# bitfur_adapter.net
KiCad netlist of a schematic drawn in EAGLE
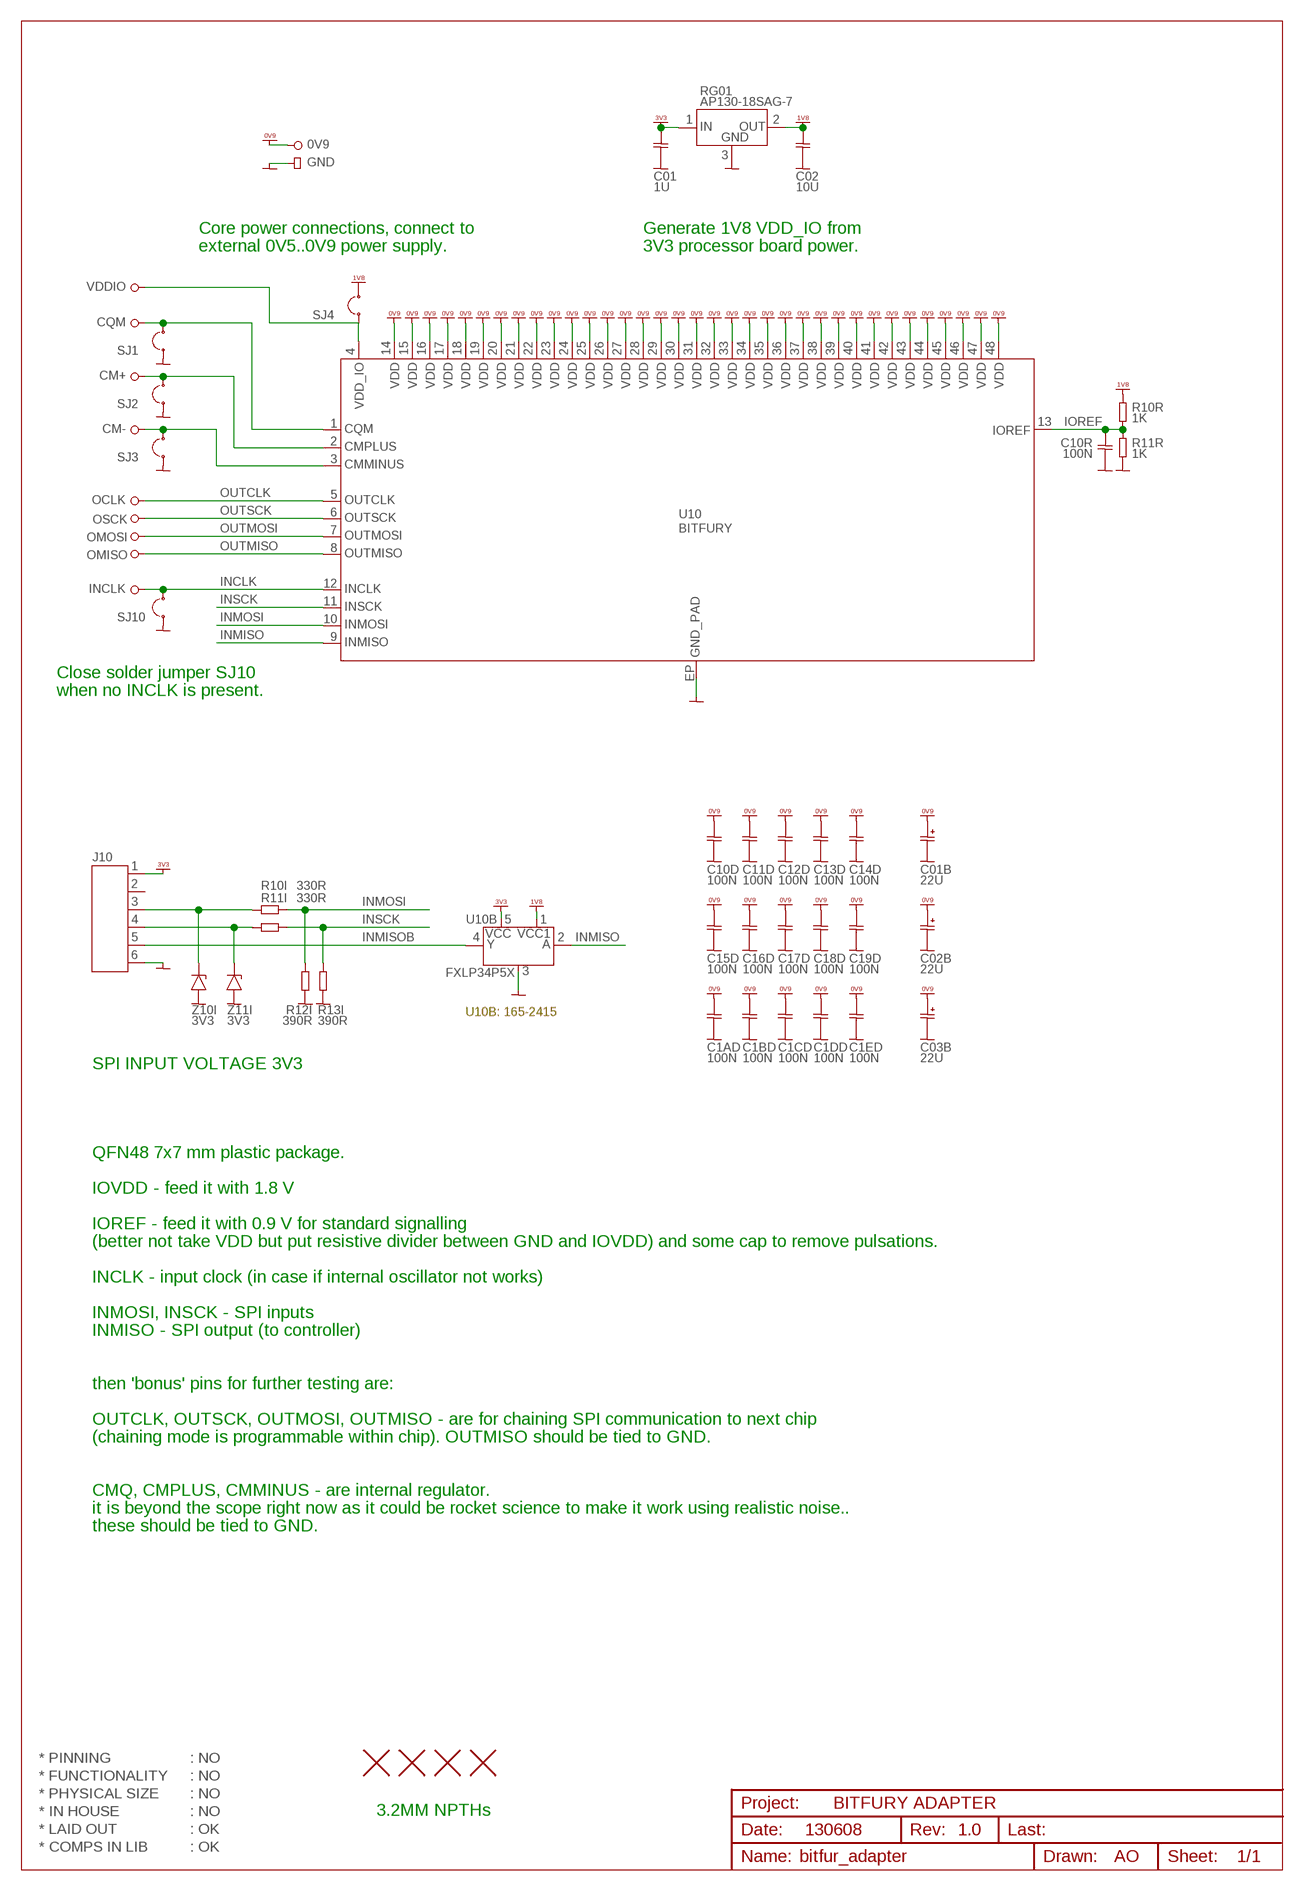
[diagram p0: schematic, sheet 1]

(export (version "E")
  (design (tool "Eeschema 10.0.6"))
  (components
    (comp (ref "0V9")
      (value "PIN_TEST_BIG")
      (footprint "eagle-import:PAD_HOLE_BIG")
      (libsource (lib "eagle-import") (part "PIN_TEST_BIG"))
    )
    (comp (ref "C01")
      (value "1U")
      (footprint "eagle-import:CAP0603")
      (libsource (lib "eagle-import") (part "CAP0603"))
    )
    (comp (ref "C1AD")
      (value "100N")
      (footprint "eagle-import:CAP0402")
      (libsource (lib "eagle-import") (part "CAP0402"))
    )
    (comp (ref "C01B")
      (value "22U")
      (footprint "eagle-import:ECAP_SMA")
      (libsource (lib "eagle-import") (part "ECAP_SMA"))
    )
    (comp (ref "C1BD")
      (value "100N")
      (footprint "eagle-import:CAP0402")
      (libsource (lib "eagle-import") (part "CAP0402"))
    )
    (comp (ref "C1CD")
      (value "100N")
      (footprint "eagle-import:CAP0402")
      (libsource (lib "eagle-import") (part "CAP0402"))
    )
    (comp (ref "C1DD")
      (value "100N")
      (footprint "eagle-import:CAP0402")
      (libsource (lib "eagle-import") (part "CAP0402"))
    )
    (comp (ref "C1ED")
      (value "100N")
      (footprint "eagle-import:CAP0402")
      (libsource (lib "eagle-import") (part "CAP0402"))
    )
    (comp (ref "C02")
      (value "10U")
      (footprint "eagle-import:CAP0603")
      (libsource (lib "eagle-import") (part "CAP0603"))
    )
    (comp (ref "C02B")
      (value "22U")
      (footprint "eagle-import:ECAP_SMA")
      (libsource (lib "eagle-import") (part "ECAP_SMA"))
    )
    (comp (ref "C03B")
      (value "22U")
      (footprint "eagle-import:ECAP_SMA")
      (libsource (lib "eagle-import") (part "ECAP_SMA"))
    )
    (comp (ref "C10D")
      (value "100N")
      (footprint "eagle-import:CAP0402")
      (libsource (lib "eagle-import") (part "CAP0402"))
    )
    (comp (ref "C10R")
      (value "100N")
      (footprint "eagle-import:CAP0402")
      (libsource (lib "eagle-import") (part "CAP0402"))
    )
    (comp (ref "C11D")
      (value "100N")
      (footprint "eagle-import:CAP0402")
      (libsource (lib "eagle-import") (part "CAP0402"))
    )
    (comp (ref "C12D")
      (value "100N")
      (footprint "eagle-import:CAP0402")
      (libsource (lib "eagle-import") (part "CAP0402"))
    )
    (comp (ref "C13D")
      (value "100N")
      (footprint "eagle-import:CAP0402")
      (libsource (lib "eagle-import") (part "CAP0402"))
    )
    (comp (ref "C14D")
      (value "100N")
      (footprint "eagle-import:CAP0402")
      (libsource (lib "eagle-import") (part "CAP0402"))
    )
    (comp (ref "C15D")
      (value "100N")
      (footprint "eagle-import:CAP0402")
      (libsource (lib "eagle-import") (part "CAP0402"))
    )
    (comp (ref "C16D")
      (value "100N")
      (footprint "eagle-import:CAP0402")
      (libsource (lib "eagle-import") (part "CAP0402"))
    )
    (comp (ref "C17D")
      (value "100N")
      (footprint "eagle-import:CAP0402")
      (libsource (lib "eagle-import") (part "CAP0402"))
    )
    (comp (ref "C18D")
      (value "100N")
      (footprint "eagle-import:CAP0402")
      (libsource (lib "eagle-import") (part "CAP0402"))
    )
    (comp (ref "C19D")
      (value "100N")
      (footprint "eagle-import:CAP0402")
      (libsource (lib "eagle-import") (part "CAP0402"))
    )
    (comp (ref "CM+")
      (value "PIN_TEST")
      (footprint "eagle-import:PAD_HOLE_0.8MM")
      (libsource (lib "eagle-import") (part "PIN_TEST"))
    )
    (comp (ref "CM-")
      (value "PIN_TEST")
      (footprint "eagle-import:PAD_HOLE_0.8MM")
      (libsource (lib "eagle-import") (part "PIN_TEST"))
    )
    (comp (ref "CQM")
      (value "PIN_TEST")
      (footprint "eagle-import:PAD_HOLE_0.8MM")
      (libsource (lib "eagle-import") (part "PIN_TEST"))
    )
    (comp (ref "H1")
      (value "HOLE_NPTH_3.2MM")
      (footprint "eagle-import:HOLE_NPTH_3.2MM")
      (libsource (lib "eagle-import") (part "HOLE_NPTH_3.2MM"))
    )
    (comp (ref "H2")
      (value "HOLE_NPTH_3.2MM")
      (footprint "eagle-import:HOLE_NPTH_3.2MM")
      (libsource (lib "eagle-import") (part "HOLE_NPTH_3.2MM"))
    )
    (comp (ref "H3")
      (value "HOLE_NPTH_3.2MM")
      (footprint "eagle-import:HOLE_NPTH_3.2MM")
      (libsource (lib "eagle-import") (part "HOLE_NPTH_3.2MM"))
    )
    (comp (ref "H4")
      (value "HOLE_NPTH_3.2MM")
      (footprint "eagle-import:HOLE_NPTH_3.2MM")
      (libsource (lib "eagle-import") (part "HOLE_NPTH_3.2MM"))
    )
    (comp (ref "INCLK")
      (value "PIN_TEST")
      (footprint "eagle-import:PAD_HOLE_0.8MM")
      (libsource (lib "eagle-import") (part "PIN_TEST"))
    )
    (comp (ref "J10")
      (value "CON_MICROMATCH_6F-TOP")
      (footprint "eagle-import:CON_MICROMATCH_TOP_6F")
      (libsource (lib "eagle-import") (part "CON_MICROMATCH_6F-TOP"))
    )
    (comp (ref "OCLK")
      (value "PIN_TEST")
      (footprint "eagle-import:PAD_HOLE_0.8MM")
      (libsource (lib "eagle-import") (part "PIN_TEST"))
    )
    (comp (ref "OMISO")
      (value "PIN_TEST")
      (footprint "eagle-import:PAD_HOLE_0.8MM")
      (libsource (lib "eagle-import") (part "PIN_TEST"))
    )
    (comp (ref "OMOSI")
      (value "PIN_TEST")
      (footprint "eagle-import:PAD_HOLE_0.8MM")
      (libsource (lib "eagle-import") (part "PIN_TEST"))
    )
    (comp (ref "OSCK")
      (value "PIN_TEST")
      (footprint "eagle-import:PAD_HOLE_0.8MM")
      (libsource (lib "eagle-import") (part "PIN_TEST"))
    )
    (comp (ref "R10I")
      (value "330R")
      (footprint "eagle-import:RES0603")
      (libsource (lib "eagle-import") (part "RES0603"))
    )
    (comp (ref "R10R")
      (value "1K")
      (footprint "eagle-import:RES0402")
      (libsource (lib "eagle-import") (part "RES0402"))
    )
    (comp (ref "R11I")
      (value "330R")
      (footprint "eagle-import:RES0603")
      (libsource (lib "eagle-import") (part "RES0603"))
    )
    (comp (ref "R11R")
      (value "1K")
      (footprint "eagle-import:RES0402")
      (libsource (lib "eagle-import") (part "RES0402"))
    )
    (comp (ref "R12I")
      (value "390R")
      (footprint "eagle-import:RES0603")
      (libsource (lib "eagle-import") (part "RES0603"))
    )
    (comp (ref "R13I")
      (value "390R")
      (footprint "eagle-import:RES0603")
      (libsource (lib "eagle-import") (part "RES0603"))
    )
    (comp (ref "RG01")
      (value "AP130-18SAG-7")
      (footprint "eagle-import:SOT23")
      (libsource (lib "eagle-import") (part "AP130-18SAG-7"))
    )
    (comp (ref "SJ1")
      (value "SJ2SJ2-S")
      (footprint "eagle-import:SJ2-S")
      (libsource (lib "eagle-import") (part "SJ2SJ2-S"))
    )
    (comp (ref "SJ2")
      (value "SJ2SJ2-S")
      (footprint "eagle-import:SJ2-S")
      (libsource (lib "eagle-import") (part "SJ2SJ2-S"))
    )
    (comp (ref "SJ3")
      (value "SJ2SJ2-S")
      (footprint "eagle-import:SJ2-S")
      (libsource (lib "eagle-import") (part "SJ2SJ2-S"))
    )
    (comp (ref "SJ4")
      (value "SJ2SJ2-S")
      (footprint "eagle-import:SJ2-S")
      (libsource (lib "eagle-import") (part "SJ2SJ2-S"))
    )
    (comp (ref "SJ10")
      (value "SJ2SJ2-S")
      (footprint "eagle-import:SJ2-S")
      (libsource (lib "eagle-import") (part "SJ2SJ2-S"))
    )
    (comp (ref "U$83")
      (value "PIN_GND")
      (footprint "eagle-import:PAD_HOLE_SQR_1.8MM")
      (libsource (lib "eagle-import") (part "PIN_GND"))
    )
    (comp (ref "U10")
      (value "BITFURY")
      (footprint "eagle-import:QNF48")
      (libsource (lib "eagle-import") (part "BITFURY"))
    )
    (comp (ref "U10B")
      (value "FXLP34P5X")
      (footprint "eagle-import:SOT23-5")
      (libsource (lib "eagle-import") (part "FXLP34P5X"))
    )
    (comp (ref "VDDIO")
      (value "PIN_TEST")
      (footprint "eagle-import:PAD_HOLE_0.8MM")
      (libsource (lib "eagle-import") (part "PIN_TEST"))
    )
    (comp (ref "Z10I")
      (value "3V3")
      (footprint "eagle-import:ZENER_SOD123")
      (libsource (lib "eagle-import") (part "ZENER_SOD123"))
    )
    (comp (ref "Z11I")
      (value "3V3")
      (footprint "eagle-import:ZENER_SOD123")
      (libsource (lib "eagle-import") (part "ZENER_SOD123"))
    )
  )
  (nets
    (net (code "1") (name "/INCLK") (class "Default")
      (node (ref "INCLK") (pin "1") (pinfunction "P$1_1") (pintype "passive"))
      (node (ref "SJ10") (pin "2") (pinfunction "P$2_2") (pintype "passive"))
      (node (ref "U10") (pin "12") (pinfunction "12.INCLK_12") (pintype "output"))
    )
    (net (code "2") (name "/INMISO") (class "Default")
      (node (ref "U10") (pin "9") (pinfunction "9.INMISO_9") (pintype "output"))
      (node (ref "U10B") (pin "2") (pinfunction "2.A_2") (pintype "passive"))
    )
    (net (code "3") (name "/INMISOB") (class "Default")
      (node (ref "J10") (pin "5") (pinfunction "5_5") (pintype "passive"))
      (node (ref "U10B") (pin "4") (pinfunction "4.Y_4") (pintype "passive"))
    )
    (net (code "4") (name "/INMOSI") (class "Default")
      (node (ref "R10I") (pin "2") (pinfunction "2_2") (pintype "passive"))
      (node (ref "R12I") (pin "2") (pinfunction "2_2") (pintype "passive"))
      (node (ref "U10") (pin "10") (pinfunction "10.INMOSI_10") (pintype "output"))
    )
    (net (code "5") (name "/INSCK") (class "Default")
      (node (ref "R11I") (pin "2") (pinfunction "2_2") (pintype "passive"))
      (node (ref "R13I") (pin "2") (pinfunction "2_2") (pintype "passive"))
      (node (ref "U10") (pin "11") (pinfunction "11.INSCK_11") (pintype "input"))
    )
    (net (code "6") (name "/IOREF") (class "Default")
      (node (ref "C10R") (pin "1") (pinfunction "1_1") (pintype "passive"))
      (node (ref "R10R") (pin "2") (pinfunction "2_2") (pintype "passive"))
      (node (ref "R11R") (pin "1") (pinfunction "1_1") (pintype "passive"))
      (node (ref "U10") (pin "13") (pinfunction "13.IOREF_13") (pintype "passive"))
    )
    (net (code "7") (name "/OUTCLK") (class "Default")
      (node (ref "OCLK") (pin "1") (pinfunction "P$1_1") (pintype "passive"))
      (node (ref "U10") (pin "5") (pinfunction "5.OUTCLK_5") (pintype "output"))
    )
    (net (code "8") (name "/OUTMISO") (class "Default")
      (node (ref "OMISO") (pin "1") (pinfunction "P$1_1") (pintype "passive"))
      (node (ref "U10") (pin "8") (pinfunction "8.OUTMISO_8") (pintype "output"))
    )
    (net (code "9") (name "/OUTMOSI") (class "Default")
      (node (ref "OMOSI") (pin "1") (pinfunction "P$1_1") (pintype "passive"))
      (node (ref "U10") (pin "7") (pinfunction "7.OUTMOSI_7") (pintype "output"))
    )
    (net (code "10") (name "/OUTSCK") (class "Default")
      (node (ref "OSCK") (pin "1") (pinfunction "P$1_1") (pintype "passive"))
      (node (ref "U10") (pin "6") (pinfunction "6.OUTSCK_6") (pintype "input"))
    )
    (net (code "11") (name "GND") (class "Default")
      (node (ref "C01") (pin "2") (pinfunction "2_2") (pintype "passive"))
      (node (ref "C01B") (pin "-") (pinfunction "-_-") (pintype "passive"))
      (node (ref "C02") (pin "2") (pinfunction "2_2") (pintype "passive"))
      (node (ref "C02B") (pin "-") (pinfunction "-_-") (pintype "passive"))
      (node (ref "C03B") (pin "-") (pinfunction "-_-") (pintype "passive"))
      (node (ref "C10D") (pin "2") (pinfunction "2_2") (pintype "passive"))
      (node (ref "C10R") (pin "2") (pinfunction "2_2") (pintype "passive"))
      (node (ref "C11D") (pin "2") (pinfunction "2_2") (pintype "passive"))
      (node (ref "C12D") (pin "2") (pinfunction "2_2") (pintype "passive"))
      (node (ref "C13D") (pin "2") (pinfunction "2_2") (pintype "passive"))
      (node (ref "C14D") (pin "2") (pinfunction "2_2") (pintype "passive"))
      (node (ref "C15D") (pin "2") (pinfunction "2_2") (pintype "passive"))
      (node (ref "C16D") (pin "2") (pinfunction "2_2") (pintype "passive"))
      (node (ref "C17D") (pin "2") (pinfunction "2_2") (pintype "passive"))
      (node (ref "C18D") (pin "2") (pinfunction "2_2") (pintype "passive"))
      (node (ref "C19D") (pin "2") (pinfunction "2_2") (pintype "passive"))
      (node (ref "C1AD") (pin "2") (pinfunction "2_2") (pintype "passive"))
      (node (ref "C1BD") (pin "2") (pinfunction "2_2") (pintype "passive"))
      (node (ref "C1CD") (pin "2") (pinfunction "2_2") (pintype "passive"))
      (node (ref "C1DD") (pin "2") (pinfunction "2_2") (pintype "passive"))
      (node (ref "C1ED") (pin "2") (pinfunction "2_2") (pintype "passive"))
      (node (ref "J10") (pin "6") (pinfunction "6_6") (pintype "passive"))
      (node (ref "R11R") (pin "2") (pinfunction "2_2") (pintype "passive"))
      (node (ref "R12I") (pin "1") (pinfunction "1_1") (pintype "passive"))
      (node (ref "R13I") (pin "1") (pinfunction "1_1") (pintype "passive"))
      (node (ref "RG01") (pin "3") (pinfunction "3.GND_3") (pintype "passive"))
      (node (ref "SJ1") (pin "1") (pinfunction "P$1_1") (pintype "passive"))
      (node (ref "SJ10") (pin "1") (pinfunction "P$1_1") (pintype "passive"))
      (node (ref "SJ2") (pin "1") (pinfunction "P$1_1") (pintype "passive"))
      (node (ref "SJ3") (pin "1") (pinfunction "P$1_1") (pintype "passive"))
      (node (ref "U$83") (pin "1") (pinfunction "P$1_1") (pintype "passive"))
      (node (ref "U10") (pin "EP") (pinfunction "EP.VSS_EP_EP") (pintype "passive"))
      (node (ref "U10") (pin "V1") (pinfunction "EP.VSS_EP_V1") (pintype "passive"))
      (node (ref "U10") (pin "V10") (pinfunction "EP.VSS_EP_V10") (pintype "passive"))
      (node (ref "U10") (pin "V11") (pinfunction "EP.VSS_EP_V11") (pintype "passive"))
      (node (ref "U10") (pin "V12") (pinfunction "EP.VSS_EP_V12") (pintype "passive"))
      (node (ref "U10") (pin "V13") (pinfunction "EP.VSS_EP_V13") (pintype "passive"))
      (node (ref "U10") (pin "V14") (pinfunction "EP.VSS_EP_V14") (pintype "passive"))
      (node (ref "U10") (pin "V15") (pinfunction "EP.VSS_EP_V15") (pintype "passive"))
      (node (ref "U10") (pin "V16") (pinfunction "EP.VSS_EP_V16") (pintype "passive"))
      (node (ref "U10") (pin "V17") (pinfunction "EP.VSS_EP_V17") (pintype "passive"))
      (node (ref "U10") (pin "V18") (pinfunction "EP.VSS_EP_V18") (pintype "passive"))
      (node (ref "U10") (pin "V19") (pinfunction "EP.VSS_EP_V19") (pintype "passive"))
      (node (ref "U10") (pin "V2") (pinfunction "EP.VSS_EP_V2") (pintype "passive"))
      (node (ref "U10") (pin "V20") (pinfunction "EP.VSS_EP_V20") (pintype "passive"))
      (node (ref "U10") (pin "V21") (pinfunction "EP.VSS_EP_V21") (pintype "passive"))
      (node (ref "U10") (pin "V22") (pinfunction "EP.VSS_EP_V22") (pintype "passive"))
      (node (ref "U10") (pin "V23") (pinfunction "EP.VSS_EP_V23") (pintype "passive"))
      (node (ref "U10") (pin "V24") (pinfunction "EP.VSS_EP_V24") (pintype "passive"))
      (node (ref "U10") (pin "V25") (pinfunction "EP.VSS_EP_V25") (pintype "passive"))
      (node (ref "U10") (pin "V3") (pinfunction "EP.VSS_EP_V3") (pintype "passive"))
      (node (ref "U10") (pin "V4") (pinfunction "EP.VSS_EP_V4") (pintype "passive"))
      (node (ref "U10") (pin "V5") (pinfunction "EP.VSS_EP_V5") (pintype "passive"))
      (node (ref "U10") (pin "V6") (pinfunction "EP.VSS_EP_V6") (pintype "passive"))
      (node (ref "U10") (pin "V7") (pinfunction "EP.VSS_EP_V7") (pintype "passive"))
      (node (ref "U10") (pin "V8") (pinfunction "EP.VSS_EP_V8") (pintype "passive"))
      (node (ref "U10") (pin "V9") (pinfunction "EP.VSS_EP_V9") (pintype "passive"))
      (node (ref "U10B") (pin "3") (pinfunction "3.GND_3") (pintype "passive"))
      (node (ref "Z10I") (pin "1") (pinfunction "+_1") (pintype "passive"))
      (node (ref "Z11I") (pin "1") (pinfunction "+_1") (pintype "passive"))
    )
    (net (code "12") (name "Net-(CM+-P$1)") (class "Default")
      (node (ref "CM+") (pin "1") (pinfunction "P$1_1") (pintype "passive"))
      (node (ref "SJ2") (pin "2") (pinfunction "P$2_2") (pintype "passive"))
      (node (ref "U10") (pin "2") (pinfunction "2.CMPLUS_2") (pintype "passive"))
    )
    (net (code "13") (name "Net-(CM--P$1)") (class "Default")
      (node (ref "CM-") (pin "1") (pinfunction "P$1_1") (pintype "passive"))
      (node (ref "SJ3") (pin "2") (pinfunction "P$2_2") (pintype "passive"))
      (node (ref "U10") (pin "3") (pinfunction "3.CMMINUS_3") (pintype "passive"))
    )
    (net (code "14") (name "Net-(CQM-P$1)") (class "Default")
      (node (ref "CQM") (pin "1") (pinfunction "P$1_1") (pintype "passive"))
      (node (ref "SJ1") (pin "2") (pinfunction "P$2_2") (pintype "passive"))
      (node (ref "U10") (pin "1") (pinfunction "1.QCM_1") (pintype "bidirectional"))
    )
    (net (code "15") (name "Net-(SJ4-P$1)") (class "Default")
      (node (ref "SJ4") (pin "1") (pinfunction "P$1_1") (pintype "passive"))
      (node (ref "U10") (pin "4") (pinfunction "4.VDD_IO_4") (pintype "passive"))
      (node (ref "VDDIO") (pin "1") (pinfunction "P$1_1") (pintype "passive"))
    )
    (net (code "16") (name "Net-(Z10I--)") (class "Default")
      (node (ref "J10") (pin "3") (pinfunction "3_3") (pintype "passive"))
      (node (ref "R10I") (pin "1") (pinfunction "1_1") (pintype "passive"))
      (node (ref "Z10I") (pin "2") (pinfunction "-_2") (pintype "passive"))
    )
    (net (code "17") (name "Net-(Z11I--)") (class "Default")
      (node (ref "J10") (pin "4") (pinfunction "4_4") (pintype "passive"))
      (node (ref "R11I") (pin "1") (pinfunction "1_1") (pintype "passive"))
      (node (ref "Z11I") (pin "2") (pinfunction "-_2") (pintype "passive"))
    )
    (net (code "18") (name "VCC_0V9") (class "Default")
      (node (ref "0V9") (pin "1") (pinfunction "P$1_1") (pintype "passive"))
      (node (ref "C01B") (pin "+") (pinfunction "+_+") (pintype "passive"))
      (node (ref "C02B") (pin "+") (pinfunction "+_+") (pintype "passive"))
      (node (ref "C03B") (pin "+") (pinfunction "+_+") (pintype "passive"))
      (node (ref "C10D") (pin "1") (pinfunction "1_1") (pintype "passive"))
      (node (ref "C11D") (pin "1") (pinfunction "1_1") (pintype "passive"))
      (node (ref "C12D") (pin "1") (pinfunction "1_1") (pintype "passive"))
      (node (ref "C13D") (pin "1") (pinfunction "1_1") (pintype "passive"))
      (node (ref "C14D") (pin "1") (pinfunction "1_1") (pintype "passive"))
      (node (ref "C15D") (pin "1") (pinfunction "1_1") (pintype "passive"))
      (node (ref "C16D") (pin "1") (pinfunction "1_1") (pintype "passive"))
      (node (ref "C17D") (pin "1") (pinfunction "1_1") (pintype "passive"))
      (node (ref "C18D") (pin "1") (pinfunction "1_1") (pintype "passive"))
      (node (ref "C19D") (pin "1") (pinfunction "1_1") (pintype "passive"))
      (node (ref "C1AD") (pin "1") (pinfunction "1_1") (pintype "passive"))
      (node (ref "C1BD") (pin "1") (pinfunction "1_1") (pintype "passive"))
      (node (ref "C1CD") (pin "1") (pinfunction "1_1") (pintype "passive"))
      (node (ref "C1DD") (pin "1") (pinfunction "1_1") (pintype "passive"))
      (node (ref "C1ED") (pin "1") (pinfunction "1_1") (pintype "passive"))
      (node (ref "U10") (pin "14") (pinfunction "14.VDD_14") (pintype "passive"))
      (node (ref "U10") (pin "15") (pinfunction "15.VDD_15") (pintype "passive"))
      (node (ref "U10") (pin "16") (pinfunction "16.VDD_16") (pintype "passive"))
      (node (ref "U10") (pin "17") (pinfunction "17.VDD_17") (pintype "passive"))
      (node (ref "U10") (pin "18") (pinfunction "18.VDD_18") (pintype "passive"))
      (node (ref "U10") (pin "19") (pinfunction "19.VDD_19") (pintype "passive"))
      (node (ref "U10") (pin "20") (pinfunction "20.VDD_20") (pintype "passive"))
      (node (ref "U10") (pin "21") (pinfunction "21.VDD_21") (pintype "passive"))
      (node (ref "U10") (pin "22") (pinfunction "22.VDD_22") (pintype "passive"))
      (node (ref "U10") (pin "23") (pinfunction "23.VDD_23") (pintype "passive"))
      (node (ref "U10") (pin "24") (pinfunction "24.VDD_24") (pintype "passive"))
      (node (ref "U10") (pin "25") (pinfunction "25.VDD_25") (pintype "passive"))
      (node (ref "U10") (pin "26") (pinfunction "26.VDD_26") (pintype "passive"))
      (node (ref "U10") (pin "27") (pinfunction "27.VDD_27") (pintype "passive"))
      (node (ref "U10") (pin "28") (pinfunction "28.VDD_28") (pintype "passive"))
      (node (ref "U10") (pin "29") (pinfunction "29.VDD_29") (pintype "passive"))
      (node (ref "U10") (pin "30") (pinfunction "30.VDD_30") (pintype "passive"))
      (node (ref "U10") (pin "31") (pinfunction "31.VDD_31") (pintype "passive"))
      (node (ref "U10") (pin "32") (pinfunction "32.VDD_32") (pintype "passive"))
      (node (ref "U10") (pin "33") (pinfunction "33.VDD_33") (pintype "passive"))
      (node (ref "U10") (pin "34") (pinfunction "34.VDD_34") (pintype "passive"))
      (node (ref "U10") (pin "35") (pinfunction "35.VDD_35") (pintype "passive"))
      (node (ref "U10") (pin "36") (pinfunction "36.VDD_36") (pintype "passive"))
      (node (ref "U10") (pin "37") (pinfunction "37.VDD_37") (pintype "passive"))
      (node (ref "U10") (pin "38") (pinfunction "38.VDD_38") (pintype "passive"))
      (node (ref "U10") (pin "39") (pinfunction "39.VDD_39") (pintype "passive"))
      (node (ref "U10") (pin "40") (pinfunction "40.VDD_40") (pintype "passive"))
      (node (ref "U10") (pin "41") (pinfunction "41.VDD_41") (pintype "passive"))
      (node (ref "U10") (pin "42") (pinfunction "42.VDD_42") (pintype "passive"))
      (node (ref "U10") (pin "43") (pinfunction "43.VDD_43") (pintype "passive"))
      (node (ref "U10") (pin "44") (pinfunction "44.VDD_44") (pintype "passive"))
      (node (ref "U10") (pin "45") (pinfunction "45.VDD_45") (pintype "passive"))
      (node (ref "U10") (pin "46") (pinfunction "46.VDD_46") (pintype "passive"))
      (node (ref "U10") (pin "47") (pinfunction "47.VDD_47") (pintype "passive"))
      (node (ref "U10") (pin "48") (pinfunction "48.VDD_48") (pintype "passive"))
    )
    (net (code "19") (name "VCC_1V8") (class "Default")
      (node (ref "C02") (pin "1") (pinfunction "1_1") (pintype "passive"))
      (node (ref "R10R") (pin "1") (pinfunction "1_1") (pintype "passive"))
      (node (ref "RG01") (pin "2") (pinfunction "2.OUT_2") (pintype "passive"))
      (node (ref "SJ4") (pin "2") (pinfunction "P$2_2") (pintype "passive"))
      (node (ref "U10B") (pin "1") (pinfunction "1.VCC1_1") (pintype "passive"))
    )
    (net (code "20") (name "VCC_3V3") (class "Default")
      (node (ref "C01") (pin "1") (pinfunction "1_1") (pintype "passive"))
      (node (ref "J10") (pin "1") (pinfunction "1_1") (pintype "passive"))
      (node (ref "RG01") (pin "1") (pinfunction "1.IN_1") (pintype "passive"))
      (node (ref "U10B") (pin "5") (pinfunction "5.VCC_5") (pintype "passive"))
    )
    (net (code "21") (name "unconnected-(J10-Pad2)") (class "Default")
      (node (ref "J10") (pin "2") (pinfunction "2_2") (pintype "passive"))
    )
  )
)
